# SpectrumAnalyzer.net
KiCad netlist of a schematic drawn in Altium Designer
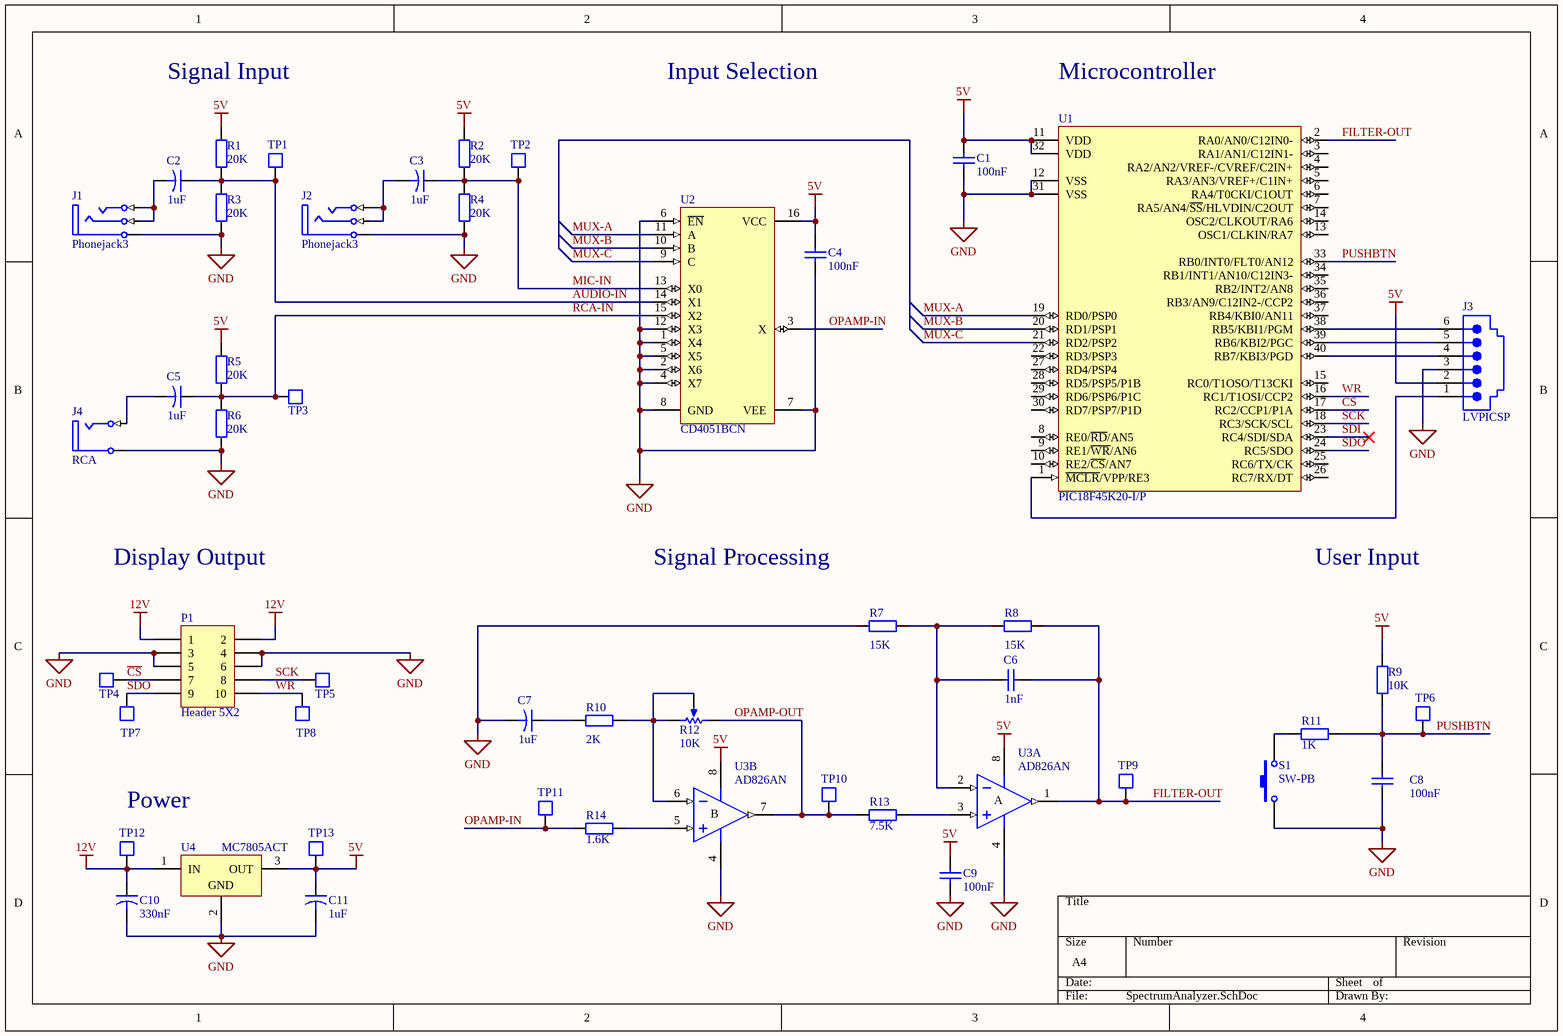
[diagram p0: SpectrumAnalyzer.SchDoc]

(export (version "E")
  (design (tool "Eeschema 10.0.6"))
  (components
    (comp (ref "C1")
      (value "100nF")
      (footprint "RAD-0.3")
      (description "Capacitor")
      (fields (field (name "Comment") "Cap") (field (name "PUBLISHER") "Altium Limited"))
      (libsource (lib "Miscellaneous Devices") (part "Cap"))
    )
    (comp (ref "C2")
      (value "1uF")
      (footprint "CAPR5-4X5")
      (description "Capacitor")
      (fields (field (name "Comment") "Cap2") (field (name "PUBLISHER") "Altium Limited"))
      (libsource (lib "Miscellaneous Devices") (part "Cap2"))
    )
    (comp (ref "C3")
      (value "1uF")
      (footprint "CAPR5-4X5")
      (description "Capacitor")
      (fields (field (name "Comment") "Cap2") (field (name "PUBLISHER") "Altium Limited"))
      (libsource (lib "Miscellaneous Devices") (part "Cap2"))
    )
    (comp (ref "C4")
      (value "100nF")
      (footprint "RAD-0.3")
      (description "Capacitor")
      (fields (field (name "Comment") "Cap") (field (name "PUBLISHER") "Altium Limited"))
      (libsource (lib "Miscellaneous Devices") (part "Cap"))
    )
    (comp (ref "C5")
      (value "1uF")
      (footprint "CAPR5-4X5")
      (description "Capacitor")
      (fields (field (name "Comment") "Cap2") (field (name "PUBLISHER") "Altium Limited"))
      (libsource (lib "Miscellaneous Devices") (part "Cap2"))
    )
    (comp (ref "C6")
      (value "1nF")
      (footprint "RAD-0.3")
      (description "Capacitor")
      (fields (field (name "Comment") "Cap") (field (name "PUBLISHER") "Altium Limited"))
      (libsource (lib "Miscellaneous Devices") (part "Cap"))
    )
    (comp (ref "C7")
      (value "1uF")
      (footprint "CAPR5-4X5")
      (description "Capacitor")
      (fields (field (name "Comment") "Cap2") (field (name "PUBLISHER") "Altium Limited"))
      (libsource (lib "Miscellaneous Devices") (part "Cap2"))
    )
    (comp (ref "C8")
      (value "100nF")
      (footprint "RAD-0.3")
      (description "Capacitor")
      (fields (field (name "Comment") "Cap") (field (name "PUBLISHER") "Altium Limited"))
      (libsource (lib "Miscellaneous Devices") (part "Cap"))
    )
    (comp (ref "C9")
      (value "100nF")
      (footprint "RAD-0.3")
      (description "Capacitor")
      (fields (field (name "Comment") "Cap") (field (name "PUBLISHER") "Altium Limited"))
      (libsource (lib "Miscellaneous Devices") (part "Cap"))
    )
    (comp (ref "C10")
      (value "330nF")
      (footprint "CAPR5-4X5")
      (description "Capacitor")
      (fields (field (name "Comment") "Cap2") (field (name "PUBLISHER") "Altium Limited"))
      (libsource (lib "Miscellaneous Devices") (part "Cap2"))
    )
    (comp (ref "C11")
      (value "1uF")
      (footprint "CAPR5-4X5")
      (description "Capacitor")
      (fields (field (name "Comment") "Cap2") (field (name "PUBLISHER") "Altium Limited"))
      (libsource (lib "Miscellaneous Devices") (part "Cap2"))
    )
    (comp (ref "J1")
      (value "Phonejack3")
      (footprint "JACK/6-V3")
      (description "Jack Socket, 1/4\" [6.5mm], Thru-Hole, Vertical, 3-Conductor Open Circuit (Non-Normalling)")
      (fields (field (name "PUBLISHER") "Altium Limited"))
      (libsource (lib "Miscellaneous Connectors") (part "Phonejack3"))
    )
    (comp (ref "J2")
      (value "Phonejack3")
      (footprint "JACK/6-V3")
      (description "Jack Socket, 1/4\" [6.5mm], Thru-Hole, Vertical, 3-Conductor Open Circuit (Non-Normalling)")
      (fields (field (name "PUBLISHER") "Altium Limited"))
      (libsource (lib "Miscellaneous Connectors") (part "Phonejack3"))
    )
    (comp (ref "J3")
      (value "LVPICSP")
      (footprint "95001-2661")
      (description "Right Angle, Low Profile, Flangeless PCB Jack")
      (fields (field (name "PUBLISHER") "Altium Limited"))
      (libsource (lib "Molex Modular Jack Right Angle") (part "95001-2661"))
    )
    (comp (ref "J4")
      (value "RCA")
      (footprint "RCA/4.5-H2")
      (description "RCA Phono Jack, Right Angle, Thru-Hole, Snap-In")
      (fields (field (name "PUBLISHER") "Altium Limited"))
      (libsource (lib "Miscellaneous Connectors") (part "RCA"))
    )
    (comp (ref "P1")
      (value "Header 5X2")
      (footprint "HDR2X5")
      (description "Header, 5-Pin, Dual row")
      (fields (field (name "PUBLISHER") "Altium Limited"))
      (libsource (lib "Miscellaneous Connectors") (part "Header 5X2"))
    )
    (comp (ref "R1")
      (value "20K")
      (footprint "AXIAL-0.4")
      (description "Resistor")
      (fields (field (name "Comment") "Res2") (field (name "PUBLISHER") "Altium Limited"))
      (libsource (lib "Miscellaneous Devices") (part "Res2"))
    )
    (comp (ref "R2")
      (value "20K")
      (footprint "AXIAL-0.4")
      (description "Resistor")
      (fields (field (name "Comment") "Res2") (field (name "PUBLISHER") "Altium Limited"))
      (libsource (lib "Miscellaneous Devices") (part "Res2"))
    )
    (comp (ref "R3")
      (value "20K")
      (footprint "AXIAL-0.4")
      (description "Resistor")
      (fields (field (name "Comment") "Res2") (field (name "PUBLISHER") "Altium Limited"))
      (libsource (lib "Miscellaneous Devices") (part "Res2"))
    )
    (comp (ref "R4")
      (value "20K")
      (footprint "AXIAL-0.4")
      (description "Resistor")
      (fields (field (name "Comment") "Res2") (field (name "PUBLISHER") "Altium Limited"))
      (libsource (lib "Miscellaneous Devices") (part "Res2"))
    )
    (comp (ref "R5")
      (value "20K")
      (footprint "AXIAL-0.4")
      (description "Resistor")
      (fields (field (name "Comment") "Res2") (field (name "PUBLISHER") "Altium Limited"))
      (libsource (lib "Miscellaneous Devices") (part "Res2"))
    )
    (comp (ref "R6")
      (value "20K")
      (footprint "AXIAL-0.4")
      (description "Resistor")
      (fields (field (name "Comment") "Res2") (field (name "PUBLISHER") "Altium Limited"))
      (libsource (lib "Miscellaneous Devices") (part "Res2"))
    )
    (comp (ref "R7")
      (value "15K")
      (footprint "AXIAL-0.4")
      (description "Resistor")
      (fields (field (name "Comment") "Res2") (field (name "PUBLISHER") "Altium Limited"))
      (libsource (lib "") (part "Res2_2"))
    )
    (comp (ref "R8")
      (value "15K")
      (footprint "AXIAL-0.4")
      (description "Resistor")
      (fields (field (name "Comment") "Res2") (field (name "PUBLISHER") "Altium Limited"))
      (libsource (lib "") (part "Res2_2"))
    )
    (comp (ref "R9")
      (value "10K")
      (footprint "AXIAL-0.4")
      (description "Resistor")
      (fields (field (name "Comment") "Res2") (field (name "PUBLISHER") "Altium Limited"))
      (libsource (lib "Miscellaneous Devices") (part "Res2"))
    )
    (comp (ref "R10")
      (value "2K")
      (footprint "AXIAL-0.4")
      (description "Resistor")
      (fields (field (name "Comment") "Res2") (field (name "PUBLISHER") "Altium Limited"))
      (libsource (lib "") (part "Res2_2"))
    )
    (comp (ref "R11")
      (value "1K")
      (footprint "AXIAL-0.4")
      (description "Resistor")
      (fields (field (name "Comment") "Res2") (field (name "PUBLISHER") "Altium Limited"))
      (libsource (lib "") (part "Res2_2"))
    )
    (comp (ref "R12")
      (value "10K")
      (footprint "VR5")
      (description "Potentiometer")
      (fields (field (name "Comment") "RPot") (field (name "PUBLISHER") "Altium Limited"))
      (libsource (lib "Miscellaneous Devices") (part "RPot"))
    )
    (comp (ref "R13")
      (value "7.5K")
      (footprint "AXIAL-0.4")
      (description "Resistor")
      (fields (field (name "Comment") "Res2") (field (name "PUBLISHER") "Altium Limited"))
      (libsource (lib "") (part "Res2_1"))
    )
    (comp (ref "R14")
      (value "1.6K")
      (footprint "AXIAL-0.4")
      (description "Resistor")
      (fields (field (name "Comment") "Res2") (field (name "PUBLISHER") "Altium Limited"))
      (libsource (lib "") (part "Res2_1"))
    )
    (comp (ref "S1")
      (value "SW-PB")
      (footprint "SPST-2")
      (description "Switch")
      (fields (field (name "PUBLISHER") "Altium Limited"))
      (libsource (lib "Miscellaneous Devices") (part "SW-PB"))
    )
    (comp (ref "TP1") (value "Test Pad") (footprint "PIN1") (libsource (lib "TestPad") (part "TestPad")))
    (comp (ref "TP2") (value "Test Pad") (footprint "PIN1") (libsource (lib "TestPad") (part "TestPad")))
    (comp (ref "TP3") (value "Test Pad") (footprint "PIN1") (libsource (lib "TestPad") (part "TestPad")))
    (comp (ref "TP4") (value "Test Pad") (footprint "PIN1") (libsource (lib "TestPad") (part "TestPad")))
    (comp (ref "TP5") (value "Test Pad") (footprint "PIN1") (libsource (lib "TestPad") (part "TestPad")))
    (comp (ref "TP6") (value "Test Pad") (footprint "PIN1") (libsource (lib "TestPad") (part "TestPad")))
    (comp (ref "TP7") (value "Test Pad") (footprint "PIN1") (libsource (lib "TestPad") (part "TestPad")))
    (comp (ref "TP8") (value "Test Pad") (footprint "PIN1") (libsource (lib "TestPad") (part "TestPad")))
    (comp (ref "TP9") (value "Test Pad") (footprint "PIN1") (libsource (lib "TestPad") (part "TestPad")))
    (comp (ref "TP10") (value "Test Pad") (footprint "PIN1") (libsource (lib "TestPad") (part "TestPad")))
    (comp (ref "TP11") (value "Test Pad") (footprint "PIN1") (libsource (lib "TestPad") (part "TestPad")))
    (comp (ref "TP12") (value "Test Pad") (footprint "PIN1") (libsource (lib "TestPad") (part "TestPad")))
    (comp (ref "TP13") (value "Test Pad") (footprint "PIN1") (libsource (lib "TestPad") (part "TestPad")))
    (comp (ref "U1")
      (value "PIC18F45K20-I/P")
      (footprint "PDIP600-P40")
      (fields (field (name "PUBLISHER") "Altium Limited"))
      (libsource (lib "Microchip Microcontroller 8-Bit PIC18") (part "PIC18F45K20-I/P"))
    )
    (comp (ref "U2")
      (value "CD4051BCN")
      (footprint "N16E")
      (description "8-Channel Analog Multiplexer/Demultiplexer")
      (fields (field (name "PUBLISHER") "Altium Limited"))
      (libsource (lib "FSC Logic Multiplexer") (part "CD4051BCN"))
    )
    (comp (ref "U3")
      (value "AD826AN")
      (footprint "N-8")
      (description "High-Speed, Low-Power Dual Operational Amplifier")
      (fields (field (name "PUBLISHER") "Altium Limited"))
      (libsource (lib "AD Operational Amplifier") (part "AD826AN"))
    )
    (comp (ref "U4")
      (value "MC7805ACT")
      (footprint "221A-04")
      (description "3-Terminal Positive Fixed Voltage Regulator")
      (fields (field (name "PUBLISHER") "Altium Limited"))
      (libsource (lib "Motorola Power Mgt Voltage Regulator") (part "MC7805ACT"))
    )
  )
  (nets
    (net (code "1") (name "/AUDIO-IN") (class "Default")
      (node (ref "C2") (pin "1") (pinfunction "1_1") (pintype "passive"))
      (node (ref "R1") (pin "1") (pinfunction "1_1") (pintype "passive"))
      (node (ref "R3") (pin "2") (pinfunction "2_2") (pintype "passive"))
      (node (ref "TP1") (pin "1") (pinfunction "1_1") (pintype "passive"))
      (node (ref "U2") (pin "14") (pinfunction "X1_14") (pintype "bidirectional"))
    )
    (net (code "2") (name "/FILTER-OUT") (class "Default")
      (node (ref "C6") (pin "2") (pinfunction "2_2") (pintype "passive"))
      (node (ref "R8") (pin "2") (pinfunction "2_2") (pintype "passive"))
      (node (ref "TP9") (pin "1") (pinfunction "1_1") (pintype "passive"))
      (node (ref "U1") (pin "2") (pinfunction "RA0/AN0/C12IN0-_2") (pintype "bidirectional"))
      (node (ref "U3") (pin "1") (pinfunction "OUT_1") (pintype "output"))
    )
    (net (code "3") (name "/MIC-IN") (class "Default")
      (node (ref "C3") (pin "1") (pinfunction "1_1") (pintype "passive"))
      (node (ref "R2") (pin "1") (pinfunction "1_1") (pintype "passive"))
      (node (ref "R4") (pin "2") (pinfunction "2_2") (pintype "passive"))
      (node (ref "TP2") (pin "1") (pinfunction "1_1") (pintype "passive"))
      (node (ref "U2") (pin "13") (pinfunction "X0_13") (pintype "bidirectional"))
    )
    (net (code "4") (name "/MUX-A") (class "Default")
      (node (ref "U1") (pin "19") (pinfunction "RD0/PSP0_19") (pintype "bidirectional"))
      (node (ref "U2") (pin "11") (pinfunction "A_11") (pintype "input"))
    )
    (net (code "5") (name "/MUX-B") (class "Default")
      (node (ref "U1") (pin "20") (pinfunction "RD1/PSP1_20") (pintype "bidirectional"))
      (node (ref "U2") (pin "10") (pinfunction "B_10") (pintype "input"))
    )
    (net (code "6") (name "/MUX-C") (class "Default")
      (node (ref "U1") (pin "21") (pinfunction "RD2/PSP2_21") (pintype "bidirectional"))
      (node (ref "U2") (pin "9") (pinfunction "C_9") (pintype "input"))
    )
    (net (code "7") (name "/OPAMP-IN") (class "Default")
      (node (ref "R14") (pin "2") (pinfunction "2_2") (pintype "passive"))
      (node (ref "TP11") (pin "1") (pinfunction "1_1") (pintype "passive"))
      (node (ref "U2") (pin "3") (pinfunction "X_3") (pintype "bidirectional"))
    )
    (net (code "8") (name "/OPAMP-OUT") (class "Default")
      (node (ref "R12") (pin "1") (pinfunction "TOP_1") (pintype "passive"))
      (node (ref "R13") (pin "2") (pinfunction "2_2") (pintype "passive"))
      (node (ref "TP10") (pin "1") (pinfunction "1_1") (pintype "passive"))
      (node (ref "U3") (pin "7") (pinfunction "OUT_7") (pintype "output"))
    )
    (net (code "9") (name "/PUSHBTN") (class "Default")
      (node (ref "C8") (pin "2") (pinfunction "2_2") (pintype "passive"))
      (node (ref "R11") (pin "2") (pinfunction "2_2") (pintype "passive"))
      (node (ref "R9") (pin "1") (pinfunction "1_1") (pintype "passive"))
      (node (ref "TP6") (pin "1") (pinfunction "1_1") (pintype "passive"))
      (node (ref "U1") (pin "33") (pinfunction "RB0/INT0/FLT0/AN12_33") (pintype "bidirectional"))
    )
    (net (code "10") (name "/RCA-IN") (class "Default")
      (node (ref "C5") (pin "1") (pinfunction "1_1") (pintype "passive"))
      (node (ref "R5") (pin "1") (pinfunction "1_1") (pintype "passive"))
      (node (ref "R6") (pin "2") (pinfunction "2_2") (pintype "passive"))
      (node (ref "TP3") (pin "1") (pinfunction "1_1") (pintype "passive"))
      (node (ref "U2") (pin "15") (pinfunction "X2_15") (pintype "bidirectional"))
    )
    (net (code "11") (name "/SCK") (class "Default")
      (node (ref "P1") (pin "8") (pinfunction "8_8") (pintype "passive"))
      (node (ref "TP5") (pin "1") (pinfunction "1_1") (pintype "passive"))
      (node (ref "U1") (pin "18") (pinfunction "RC3/SCK/SCL_18") (pintype "bidirectional"))
    )
    (net (code "12") (name "/SDI") (class "Default")
      (node (ref "U1") (pin "23") (pinfunction "RC4/SDI/SDA_23") (pintype "bidirectional+no_connect"))
    )
    (net (code "13") (name "/SDO") (class "Default")
      (node (ref "P1") (pin "9") (pinfunction "9_9") (pintype "passive"))
      (node (ref "TP7") (pin "1") (pinfunction "1_1") (pintype "passive"))
      (node (ref "U1") (pin "24") (pinfunction "RC5/SDO_24") (pintype "bidirectional"))
    )
    (net (code "14") (name "/WR") (class "Default")
      (node (ref "P1") (pin "10") (pinfunction "10_10") (pintype "passive"))
      (node (ref "TP8") (pin "1") (pinfunction "1_1") (pintype "passive"))
      (node (ref "U1") (pin "16") (pinfunction "RC1/T1OSI/CCP2_16") (pintype "bidirectional"))
    )
    (net (code "15") (name "/~{CS}") (class "Default")
      (node (ref "P1") (pin "7") (pinfunction "7_7") (pintype "passive"))
      (node (ref "TP4") (pin "1") (pinfunction "1_1") (pintype "passive"))
      (node (ref "U1") (pin "17") (pinfunction "RC2/CCP1/P1A_17") (pintype "bidirectional"))
    )
    (net (code "16") (name "5V") (class "Default")
      (node (ref "C1") (pin "1") (pinfunction "1_1") (pintype "passive"))
      (node (ref "C11") (pin "1") (pinfunction "1_1") (pintype "passive"))
      (node (ref "C4") (pin "1") (pinfunction "1_1") (pintype "passive"))
      (node (ref "C9") (pin "1") (pinfunction "1_1") (pintype "passive"))
      (node (ref "J3") (pin "2") (pinfunction "2_2") (pintype "passive"))
      (node (ref "R1") (pin "2") (pinfunction "2_2") (pintype "passive"))
      (node (ref "R2") (pin "2") (pinfunction "2_2") (pintype "passive"))
      (node (ref "R5") (pin "2") (pinfunction "2_2") (pintype "passive"))
      (node (ref "R9") (pin "2") (pinfunction "2_2") (pintype "passive"))
      (node (ref "TP13") (pin "1") (pinfunction "1_1") (pintype "passive"))
      (node (ref "U1") (pin "11") (pinfunction "VDD_11") (pintype "power_in"))
      (node (ref "U1") (pin "32") (pinfunction "VDD_32") (pintype "power_in"))
      (node (ref "U2") (pin "16") (pinfunction "VCC_16") (pintype "power_in"))
      (node (ref "U3") (pin "8") (pinfunction "V+_8") (pintype "power_in"))
      (node (ref "U4") (pin "3") (pinfunction "OUT_3") (pintype "power_in"))
    )
    (net (code "17") (name "12V") (class "Default")
      (node (ref "C10") (pin "1") (pinfunction "1_1") (pintype "passive"))
      (node (ref "P1") (pin "1") (pinfunction "1_1") (pintype "passive"))
      (node (ref "P1") (pin "2") (pinfunction "2_2") (pintype "passive"))
      (node (ref "TP12") (pin "1") (pinfunction "1_1") (pintype "passive"))
      (node (ref "U4") (pin "1") (pinfunction "IN_1") (pintype "power_in"))
    )
    (net (code "18") (name "GND") (class "Default")
      (node (ref "C1") (pin "2") (pinfunction "2_2") (pintype "passive"))
      (node (ref "C10") (pin "2") (pinfunction "2_2") (pintype "passive"))
      (node (ref "C11") (pin "2") (pinfunction "2_2") (pintype "passive"))
      (node (ref "C4") (pin "2") (pinfunction "2_2") (pintype "passive"))
      (node (ref "C7") (pin "2") (pinfunction "2_2") (pintype "passive"))
      (node (ref "C8") (pin "1") (pinfunction "1_1") (pintype "passive"))
      (node (ref "C9") (pin "2") (pinfunction "2_2") (pintype "passive"))
      (node (ref "J1") (pin "5") (pinfunction "S_5") (pintype "power_in"))
      (node (ref "J2") (pin "5") (pinfunction "S_5") (pintype "power_in"))
      (node (ref "J3") (pin "3") (pinfunction "3_3") (pintype "passive"))
      (node (ref "J4") (pin "1A") (pinfunction "Ground_1A") (pintype "power_in"))
      (node (ref "P1") (pin "3") (pinfunction "3_3") (pintype "passive"))
      (node (ref "P1") (pin "4") (pinfunction "4_4") (pintype "passive"))
      (node (ref "P1") (pin "5") (pinfunction "5_5") (pintype "passive"))
      (node (ref "P1") (pin "6") (pinfunction "6_6") (pintype "passive"))
      (node (ref "R3") (pin "1") (pinfunction "1_1") (pintype "passive"))
      (node (ref "R4") (pin "1") (pinfunction "1_1") (pintype "passive"))
      (node (ref "R6") (pin "1") (pinfunction "1_1") (pintype "passive"))
      (node (ref "R7") (pin "1") (pinfunction "1_1") (pintype "passive"))
      (node (ref "S1") (pin "1") (pinfunction "1_1") (pintype "passive"))
      (node (ref "U1") (pin "12") (pinfunction "VSS_12") (pintype "power_in"))
      (node (ref "U1") (pin "31") (pinfunction "VSS_31") (pintype "power_in"))
      (node (ref "U2") (pin "1") (pinfunction "X4_1") (pintype "bidirectional"))
      (node (ref "U2") (pin "12") (pinfunction "X3_12") (pintype "bidirectional"))
      (node (ref "U2") (pin "2") (pinfunction "X6_2") (pintype "bidirectional"))
      (node (ref "U2") (pin "4") (pinfunction "X7_4") (pintype "bidirectional"))
      (node (ref "U2") (pin "5") (pinfunction "X5_5") (pintype "bidirectional"))
      (node (ref "U2") (pin "6") (pinfunction "~{EN}_6") (pintype "input"))
      (node (ref "U2") (pin "7") (pinfunction "VEE_7") (pintype "power_in"))
      (node (ref "U2") (pin "8") (pinfunction "GND_8") (pintype "power_in"))
      (node (ref "U3") (pin "4") (pinfunction "V-_4") (pintype "power_in"))
      (node (ref "U4") (pin "2") (pinfunction "GND_2") (pintype "power_in"))
    )
    (net (code "19") (name "Net-(C7-Pad1)") (class "Default")
      (node (ref "C7") (pin "1") (pinfunction "1_1") (pintype "passive"))
      (node (ref "R10") (pin "1") (pinfunction "1_1") (pintype "passive"))
    )
    (net (code "20") (name "Net-(J1-R)") (class "Default")
      (node (ref "C2") (pin "2") (pinfunction "2_2") (pintype "passive"))
      (node (ref "J1") (pin "1") (pinfunction "T_1") (pintype "input"))
      (node (ref "J1") (pin "3") (pinfunction "R_3") (pintype "input"))
    )
    (net (code "21") (name "Net-(J2-R)") (class "Default")
      (node (ref "C3") (pin "2") (pinfunction "2_2") (pintype "passive"))
      (node (ref "J2") (pin "1") (pinfunction "T_1") (pintype "input"))
      (node (ref "J2") (pin "3") (pinfunction "R_3") (pintype "input"))
    )
    (net (code "22") (name "Net-(J4-Signal)") (class "Default")
      (node (ref "C5") (pin "2") (pinfunction "2_2") (pintype "passive"))
      (node (ref "J4") (pin "2B") (pinfunction "Signal_2B") (pintype "input"))
    )
    (net (code "23") (name "Net-(R11-Pad1)") (class "Default")
      (node (ref "R11") (pin "1") (pinfunction "1_1") (pintype "passive"))
      (node (ref "S1") (pin "2") (pinfunction "2_2") (pintype "passive"))
    )
    (net (code "24") (name "Net-(R12-BOT)") (class "Default")
      (node (ref "R10") (pin "2") (pinfunction "2_2") (pintype "passive"))
      (node (ref "R12") (pin "2") (pinfunction "BOT_2") (pintype "passive"))
      (node (ref "R12") (pin "3") (pinfunction "TAP_3") (pintype "passive"))
      (node (ref "U3") (pin "6") (pinfunction "IN-_6") (pintype "input"))
    )
    (net (code "25") (name "Net-(U1-RB5{slash}KBI1{slash}PGM)") (class "Default")
      (node (ref "J3") (pin "6") (pinfunction "6_6") (pintype "passive"))
      (node (ref "U1") (pin "38") (pinfunction "RB5/KBI1/PGM_38") (pintype "bidirectional"))
    )
    (net (code "26") (name "Net-(U1-RB6{slash}KBI2{slash}PGC)") (class "Default")
      (node (ref "J3") (pin "5") (pinfunction "5_5") (pintype "passive"))
      (node (ref "U1") (pin "39") (pinfunction "RB6/KBI2/PGC_39") (pintype "bidirectional"))
    )
    (net (code "27") (name "Net-(U1-RB7{slash}KBI3{slash}PGD)") (class "Default")
      (node (ref "J3") (pin "4") (pinfunction "4_4") (pintype "passive"))
      (node (ref "U1") (pin "40") (pinfunction "RB7/KBI3/PGD_40") (pintype "bidirectional"))
    )
    (net (code "28") (name "Net-(U1-~{MCLR}{slash}VPP{slash}RE3)") (class "Default")
      (node (ref "J3") (pin "1") (pinfunction "1_1") (pintype "passive"))
      (node (ref "U1") (pin "1") (pinfunction "~{MCLR}/VPP/RE3_1") (pintype "input"))
    )
    (net (code "29") (name "Net-(U3A-IN+)") (class "Default")
      (node (ref "R13") (pin "1") (pinfunction "1_1") (pintype "passive"))
      (node (ref "U3") (pin "3") (pinfunction "IN+_3") (pintype "input"))
    )
    (net (code "30") (name "Net-(U3A-IN-)") (class "Default")
      (node (ref "C6") (pin "1") (pinfunction "1_1") (pintype "passive"))
      (node (ref "R7") (pin "2") (pinfunction "2_2") (pintype "passive"))
      (node (ref "R8") (pin "1") (pinfunction "1_1") (pintype "passive"))
      (node (ref "U3") (pin "2") (pinfunction "IN-_2") (pintype "input"))
    )
    (net (code "31") (name "Net-(U3B-IN+)") (class "Default")
      (node (ref "R14") (pin "1") (pinfunction "1_1") (pintype "passive"))
      (node (ref "U3") (pin "5") (pinfunction "IN+_5") (pintype "input"))
    )
    (net (code "32") (name "unconnected-(U1-OSC1{slash}CLKIN{slash}RA7-Pad13)") (class "Default")
      (node (ref "U1") (pin "13") (pinfunction "OSC1/CLKIN/RA7_13") (pintype "bidirectional"))
    )
    (net (code "33") (name "unconnected-(U1-OSC2{slash}CLKOUT{slash}RA6-Pad14)") (class "Default")
      (node (ref "U1") (pin "14") (pinfunction "OSC2/CLKOUT/RA6_14") (pintype "bidirectional"))
    )
    (net (code "34") (name "unconnected-(U1-RA1{slash}AN1{slash}C12IN1--Pad3)") (class "Default")
      (node (ref "U1") (pin "3") (pinfunction "RA1/AN1/C12IN1-_3") (pintype "bidirectional"))
    )
    (net (code "35") (name "unconnected-(U1-RA2{slash}AN2{slash}VREF-{slash}CVREF{slash}C2IN+-Pad4)") (class "Default")
      (node (ref "U1") (pin "4") (pinfunction "RA2/AN2/VREF-/CVREF/C2IN+_4") (pintype "bidirectional"))
    )
    (net (code "36") (name "unconnected-(U1-RA3{slash}AN3{slash}VREF+{slash}C1IN+-Pad5)") (class "Default")
      (node (ref "U1") (pin "5") (pinfunction "RA3/AN3/VREF+/C1IN+_5") (pintype "bidirectional"))
    )
    (net (code "37") (name "unconnected-(U1-RA4{slash}T0CKI{slash}C1OUT-Pad6)") (class "Default")
      (node (ref "U1") (pin "6") (pinfunction "RA4/T0CKI/C1OUT_6") (pintype "bidirectional"))
    )
    (net (code "38") (name "unconnected-(U1-RA5{slash}AN4{slash}~{SS}{slash}HLVDIN{slash}C2OUT-Pad7)") (class "Default")
      (node (ref "U1") (pin "7") (pinfunction "RA5/AN4/~{SS}/HLVDIN/C2OUT_7") (pintype "bidirectional"))
    )
    (net (code "39") (name "unconnected-(U1-RB1{slash}INT1{slash}AN10{slash}C12IN3--Pad34)") (class "Default")
      (node (ref "U1") (pin "34") (pinfunction "RB1/INT1/AN10/C12IN3-_34") (pintype "bidirectional"))
    )
    (net (code "40") (name "unconnected-(U1-RB2{slash}INT2{slash}AN8-Pad35)") (class "Default")
      (node (ref "U1") (pin "35") (pinfunction "RB2/INT2/AN8_35") (pintype "bidirectional"))
    )
    (net (code "41") (name "unconnected-(U1-RB3{slash}AN9{slash}C12IN2-{slash}CCP2-Pad36)") (class "Default")
      (node (ref "U1") (pin "36") (pinfunction "RB3/AN9/C12IN2-/CCP2_36") (pintype "bidirectional"))
    )
    (net (code "42") (name "unconnected-(U1-RB4{slash}KBI0{slash}AN11-Pad37)") (class "Default")
      (node (ref "U1") (pin "37") (pinfunction "RB4/KBI0/AN11_37") (pintype "bidirectional"))
    )
    (net (code "43") (name "unconnected-(U1-RC0{slash}T1OSO{slash}T13CKI-Pad15)") (class "Default")
      (node (ref "U1") (pin "15") (pinfunction "RC0/T1OSO/T13CKI_15") (pintype "bidirectional"))
    )
    (net (code "44") (name "unconnected-(U1-RC6{slash}TX{slash}CK-Pad25)") (class "Default")
      (node (ref "U1") (pin "25") (pinfunction "RC6/TX/CK_25") (pintype "bidirectional"))
    )
    (net (code "45") (name "unconnected-(U1-RC7{slash}RX{slash}DT-Pad26)") (class "Default")
      (node (ref "U1") (pin "26") (pinfunction "RC7/RX/DT_26") (pintype "bidirectional"))
    )
    (net (code "46") (name "unconnected-(U1-RD3{slash}PSP3-Pad22)") (class "Default")
      (node (ref "U1") (pin "22") (pinfunction "RD3/PSP3_22") (pintype "bidirectional"))
    )
    (net (code "47") (name "unconnected-(U1-RD4{slash}PSP4-Pad27)") (class "Default")
      (node (ref "U1") (pin "27") (pinfunction "RD4/PSP4_27") (pintype "bidirectional"))
    )
    (net (code "48") (name "unconnected-(U1-RD5{slash}PSP5{slash}P1B-Pad28)") (class "Default")
      (node (ref "U1") (pin "28") (pinfunction "RD5/PSP5/P1B_28") (pintype "bidirectional"))
    )
    (net (code "49") (name "unconnected-(U1-RD6{slash}PSP6{slash}P1C-Pad29)") (class "Default")
      (node (ref "U1") (pin "29") (pinfunction "RD6/PSP6/P1C_29") (pintype "bidirectional"))
    )
    (net (code "50") (name "unconnected-(U1-RD7{slash}PSP7{slash}P1D-Pad30)") (class "Default")
      (node (ref "U1") (pin "30") (pinfunction "RD7/PSP7/P1D_30") (pintype "bidirectional"))
    )
    (net (code "51") (name "unconnected-(U1-RE0{slash}~{RD}{slash}AN5-Pad8)") (class "Default")
      (node (ref "U1") (pin "8") (pinfunction "RE0/~{RD}/AN5_8") (pintype "bidirectional"))
    )
    (net (code "52") (name "unconnected-(U1-RE1{slash}~{WR}{slash}AN6-Pad9)") (class "Default")
      (node (ref "U1") (pin "9") (pinfunction "RE1/~{WR}/AN6_9") (pintype "bidirectional"))
    )
    (net (code "53") (name "unconnected-(U1-RE2{slash}~{CS}{slash}AN7-Pad10)") (class "Default")
      (node (ref "U1") (pin "10") (pinfunction "RE2/~{CS}/AN7_10") (pintype "bidirectional"))
    )
  )
)
